# triggerbox.net
KiCad netlist of a schematic drawn in EAGLE
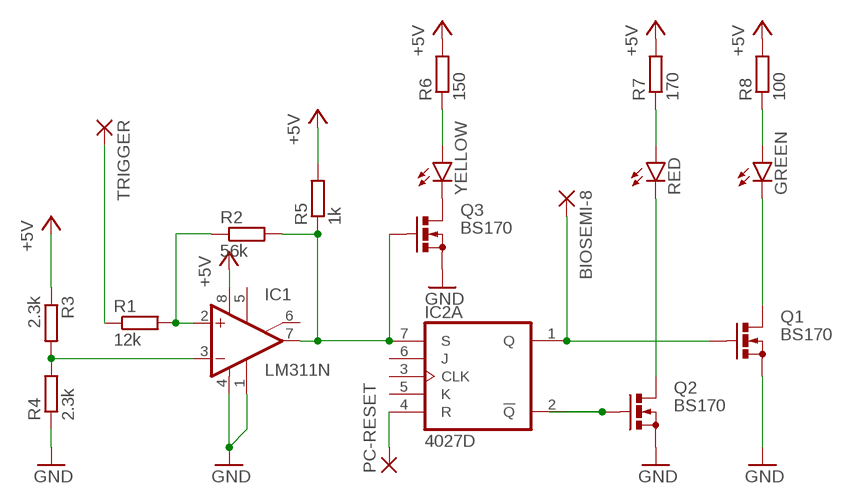
[diagram p0: schematic, sheet 1]

(export (version "E")
  (design (tool "Eeschema 10.0.6"))
  (components
    (comp (ref "BIOSEMI-8")
      (value "WIREPAD1,6/0,8")
      (footprint "eagle-import:1,6_0,8")
      (libsource (lib "eagle-import") (part "WIREPAD1,6/0,8"))
    )
    (comp (ref "GREEN")
      (value "LED5MM")
      (footprint "eagle-import:LED5MM")
      (libsource (lib "eagle-import") (part "LED5MM"))
    )
    (comp (ref "IC1")
      (value "LM311N")
      (footprint "eagle-import:DIL08")
      (libsource (lib "eagle-import") (part "LM311N"))
    )
    (comp (ref "IC2")
      (value "4027D")
      (footprint "eagle-import:SO16")
      (libsource (lib "eagle-import") (part "4027D"))
    )
    (comp (ref "PC-RESET")
      (value "WIREPAD1,6/0,8")
      (footprint "eagle-import:1,6_0,8")
      (libsource (lib "eagle-import") (part "WIREPAD1,6/0,8"))
    )
    (comp (ref "Q1")
      (value "BS170")
      (footprint "eagle-import:SOT54E")
      (libsource (lib "eagle-import") (part "BS170"))
    )
    (comp (ref "Q2")
      (value "BS170")
      (footprint "eagle-import:SOT54E")
      (libsource (lib "eagle-import") (part "BS170"))
    )
    (comp (ref "Q3")
      (value "BS170")
      (footprint "eagle-import:SOT54E")
      (libsource (lib "eagle-import") (part "BS170"))
    )
    (comp (ref "R1")
      (value "12k")
      (footprint "eagle-import:R0805")
      (libsource (lib "eagle-import") (part "R-EU_R0805"))
    )
    (comp (ref "R2")
      (value "56k")
      (footprint "eagle-import:R0805")
      (libsource (lib "eagle-import") (part "R-EU_R0805"))
    )
    (comp (ref "R3")
      (value "2.3k")
      (footprint "eagle-import:R0805")
      (libsource (lib "eagle-import") (part "R-EU_R0805"))
    )
    (comp (ref "R4")
      (value "2.3k")
      (footprint "eagle-import:R0805")
      (libsource (lib "eagle-import") (part "R-EU_R0805"))
    )
    (comp (ref "R5")
      (value "1k")
      (footprint "eagle-import:R0805")
      (libsource (lib "eagle-import") (part "R-EU_R0805"))
    )
    (comp (ref "R6")
      (value "150")
      (footprint "eagle-import:R0805")
      (libsource (lib "eagle-import") (part "R-EU_R0805"))
    )
    (comp (ref "R7")
      (value "170")
      (footprint "eagle-import:R0805")
      (libsource (lib "eagle-import") (part "R-EU_R0805"))
    )
    (comp (ref "R8")
      (value "100")
      (footprint "eagle-import:R0805")
      (libsource (lib "eagle-import") (part "R-EU_R0805"))
    )
    (comp (ref "RED")
      (value "LED5MM")
      (footprint "eagle-import:LED5MM")
      (libsource (lib "eagle-import") (part "LED5MM"))
    )
    (comp (ref "TRIGGER")
      (value "WIREPAD1,6/0,8")
      (footprint "eagle-import:1,6_0,8")
      (libsource (lib "eagle-import") (part "WIREPAD1,6/0,8"))
    )
    (comp (ref "YELLOW")
      (value "LED5MM")
      (footprint "eagle-import:LED5MM")
      (libsource (lib "eagle-import") (part "LED5MM"))
    )
  )
  (nets
    (net (code "1") (name "+5V") (class "Default")
      (node (ref "IC1") (pin "8") (pinfunction "V+_8") (pintype "power_in"))
      (node (ref "R3") (pin "1") (pinfunction "1_1") (pintype "passive"))
      (node (ref "R5") (pin "2") (pinfunction "2_2") (pintype "passive"))
      (node (ref "R6") (pin "2") (pinfunction "2_2") (pintype "passive"))
      (node (ref "R7") (pin "2") (pinfunction "2_2") (pintype "passive"))
      (node (ref "R8") (pin "2") (pinfunction "2_2") (pintype "passive"))
    )
    (net (code "2") (name "GND") (class "Default")
      (node (ref "IC1") (pin "1") (pinfunction "GND_1") (pintype "passive"))
      (node (ref "IC1") (pin "4") (pinfunction "V-_4") (pintype "power_in"))
      (node (ref "Q1") (pin "S") (pinfunction "S_S") (pintype "passive"))
      (node (ref "Q2") (pin "S") (pinfunction "S_S") (pintype "passive"))
      (node (ref "Q3") (pin "S") (pinfunction "S_S") (pintype "passive"))
      (node (ref "R4") (pin "1") (pinfunction "1_1") (pintype "passive"))
    )
    (net (code "3") (name "Net-(BIOSEMI-8-P)") (class "Default")
      (node (ref "BIOSEMI-8") (pin "1") (pinfunction "P_1") (pintype "passive"))
      (node (ref "IC2") (pin "1") (pinfunction "Q_1") (pintype "output"))
      (node (ref "Q1") (pin "G") (pinfunction "G_G") (pintype "passive"))
    )
    (net (code "4") (name "Net-(GREEN-C)") (class "Default")
      (node (ref "GREEN") (pin "K") (pinfunction "C_K") (pintype "passive"))
      (node (ref "Q1") (pin "D") (pinfunction "D_D") (pintype "passive"))
    )
    (net (code "5") (name "Net-(GREEN-PadA)") (class "Default")
      (node (ref "GREEN") (pin "A") (pinfunction "A_A") (pintype "passive"))
      (node (ref "R8") (pin "1") (pinfunction "1_1") (pintype "passive"))
    )
    (net (code "6") (name "Net-(IC1-+IN)") (class "Default")
      (node (ref "IC1") (pin "2") (pinfunction "+IN_2") (pintype "input"))
      (node (ref "R1") (pin "2") (pinfunction "2_2") (pintype "passive"))
      (node (ref "R2") (pin "1") (pinfunction "1_1") (pintype "passive"))
    )
    (net (code "7") (name "Net-(IC1--IN)") (class "Default")
      (node (ref "IC1") (pin "3") (pinfunction "-IN_3") (pintype "input"))
      (node (ref "R3") (pin "2") (pinfunction "2_2") (pintype "passive"))
      (node (ref "R4") (pin "2") (pinfunction "2_2") (pintype "passive"))
    )
    (net (code "8") (name "Net-(IC1-OUT)") (class "Default")
      (node (ref "IC1") (pin "7") (pinfunction "OUT_7") (pintype "output"))
      (node (ref "IC2") (pin "7") (pinfunction "S_7") (pintype "input"))
      (node (ref "Q3") (pin "G") (pinfunction "G_G") (pintype "passive"))
      (node (ref "R2") (pin "2") (pinfunction "2_2") (pintype "passive"))
      (node (ref "R5") (pin "1") (pinfunction "1_1") (pintype "passive"))
    )
    (net (code "9") (name "Net-(IC2A-R)") (class "Default")
      (node (ref "IC2") (pin "4") (pinfunction "R_4") (pintype "input"))
      (node (ref "PC-RESET") (pin "1") (pinfunction "P_1") (pintype "passive"))
    )
    (net (code "10") (name "Net-(IC2A-~{Q})") (class "Default")
      (node (ref "IC2") (pin "2") (pinfunction "~{Q}_2") (pintype "output"))
      (node (ref "Q2") (pin "G") (pinfunction "G_G") (pintype "passive"))
    )
    (net (code "11") (name "Net-(R6-Pad1)") (class "Default")
      (node (ref "R6") (pin "1") (pinfunction "1_1") (pintype "passive"))
      (node (ref "YELLOW") (pin "A") (pinfunction "A_A") (pintype "passive"))
    )
    (net (code "12") (name "Net-(R7-Pad1)") (class "Default")
      (node (ref "R7") (pin "1") (pinfunction "1_1") (pintype "passive"))
      (node (ref "RED") (pin "A") (pinfunction "A_A") (pintype "passive"))
    )
    (net (code "13") (name "Net-(RED-C)") (class "Default")
      (node (ref "Q2") (pin "D") (pinfunction "D_D") (pintype "passive"))
      (node (ref "RED") (pin "K") (pinfunction "C_K") (pintype "passive"))
    )
    (net (code "14") (name "Net-(TRIGGER-P)") (class "Default")
      (node (ref "R1") (pin "1") (pinfunction "1_1") (pintype "passive"))
      (node (ref "TRIGGER") (pin "1") (pinfunction "P_1") (pintype "passive"))
    )
    (net (code "15") (name "Net-(YELLOW-C)") (class "Default")
      (node (ref "Q3") (pin "D") (pinfunction "D_D") (pintype "passive"))
      (node (ref "YELLOW") (pin "K") (pinfunction "C_K") (pintype "passive"))
    )
    (net (code "16") (name "unconnected-(IC1-ON-Pad5)") (class "Default")
      (node (ref "IC1") (pin "5") (pinfunction "ON_5") (pintype "passive"))
    )
    (net (code "17") (name "unconnected-(IC1-ON{slash}STR-Pad6)") (class "Default")
      (node (ref "IC1") (pin "6") (pinfunction "ON/STR_6") (pintype "passive"))
    )
    (net (code "18") (name "unconnected-(IC2A-CLK-Pad3)") (class "Default")
      (node (ref "IC2") (pin "3") (pinfunction "CLK_3") (pintype "input"))
    )
    (net (code "19") (name "unconnected-(IC2A-J-Pad6)") (class "Default")
      (node (ref "IC2") (pin "6") (pinfunction "J_6") (pintype "input"))
    )
    (net (code "20") (name "unconnected-(IC2A-K-Pad5)") (class "Default")
      (node (ref "IC2") (pin "5") (pinfunction "K_5") (pintype "input"))
    )
  )
)
